# metal_mill_wiring.net
KiCad netlist of a schematic drawn in EAGLE
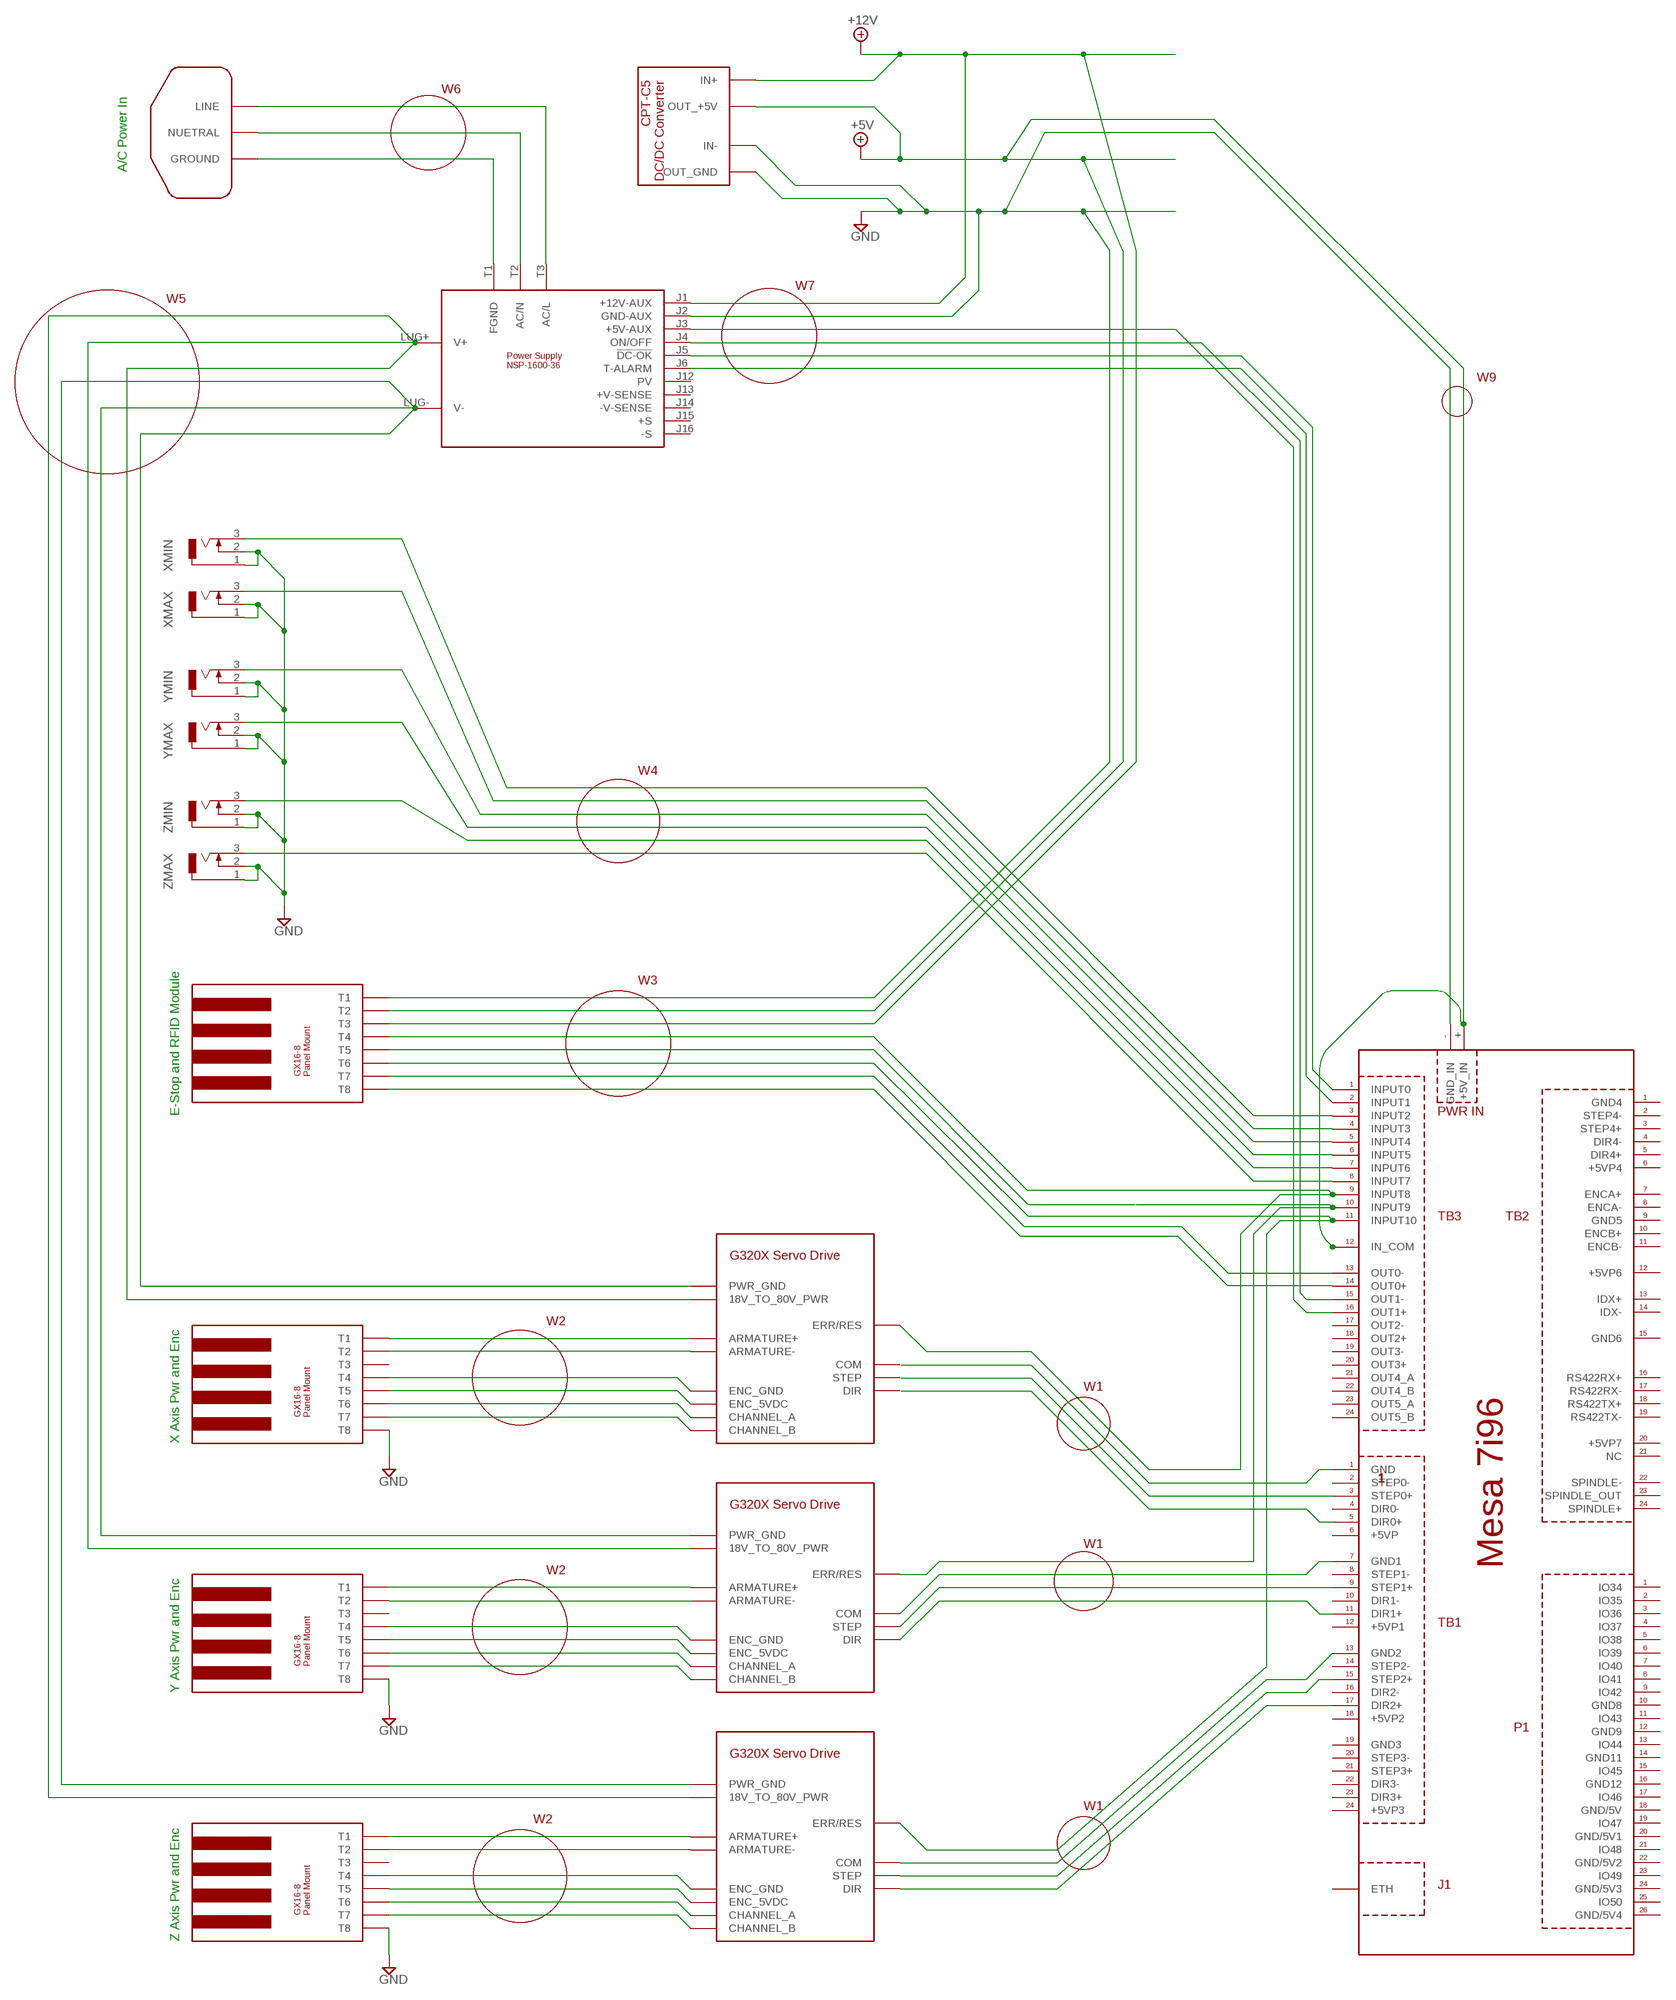
[diagram p0: schematic, sheet 1]

(export (version "E")
  (design (tool "Eeschema 10.0.6"))
  (components
    (comp (ref "U$1")
      (value "MESA_7I96")
      (footprint "eagle-import:7I96")
      (libsource (lib "eagle-import") (part "MESA_7I96"))
    )
    (comp (ref "U$2")
      (value "G320X")
      (footprint "eagle-import:G320X")
      (libsource (lib "eagle-import") (part "G320X"))
    )
    (comp (ref "U$3")
      (value "G320X")
      (footprint "eagle-import:G320X")
      (libsource (lib "eagle-import") (part "G320X"))
    )
    (comp (ref "U$4")
      (value "G320X")
      (footprint "eagle-import:G320X")
      (libsource (lib "eagle-import") (part "G320X"))
    )
    (comp (ref "U$5")
      (value "NSP-1600-36")
      (footprint "eagle-import:NSP-1600-36")
      (libsource (lib "eagle-import") (part "NSP-1600-36"))
    )
    (comp (ref "U$6")
      (value "CPT-C5")
      (footprint "eagle-import:CPT-C5")
      (libsource (lib "eagle-import") (part "CPT-C5"))
    )
    (comp (ref "U$7")
      (value "GX16-8")
      (footprint "eagle-import:GX16-8")
      (libsource (lib "eagle-import") (part "GX16-8"))
    )
    (comp (ref "U$8")
      (value "GX16-8")
      (footprint "eagle-import:GX16-8")
      (libsource (lib "eagle-import") (part "GX16-8"))
    )
    (comp (ref "U$9")
      (value "AC_JACK")
      (footprint "eagle-import:AC_JACK")
      (libsource (lib "eagle-import") (part "AC_JACK"))
    )
    (comp (ref "XMAX")
      (value "DCJ0202")
      (footprint "eagle-import:DCJ0202")
      (libsource (lib "eagle-import") (part "DCJ0202"))
    )
    (comp (ref "XMIN")
      (value "DCJ0202")
      (footprint "eagle-import:DCJ0202")
      (libsource (lib "eagle-import") (part "DCJ0202"))
    )
    (comp (ref "X_AXIS")
      (value "GX16-8")
      (footprint "eagle-import:GX16-8")
      (libsource (lib "eagle-import") (part "GX16-8"))
    )
    (comp (ref "X_AXIS1")
      (value "GX16-8")
      (footprint "eagle-import:GX16-8")
      (libsource (lib "eagle-import") (part "GX16-8"))
    )
    (comp (ref "YMAX")
      (value "DCJ0202")
      (footprint "eagle-import:DCJ0202")
      (libsource (lib "eagle-import") (part "DCJ0202"))
    )
    (comp (ref "YMIN")
      (value "DCJ0202")
      (footprint "eagle-import:DCJ0202")
      (libsource (lib "eagle-import") (part "DCJ0202"))
    )
    (comp (ref "ZMAX")
      (value "DCJ0202")
      (footprint "eagle-import:DCJ0202")
      (libsource (lib "eagle-import") (part "DCJ0202"))
    )
    (comp (ref "ZMIN")
      (value "DCJ0202")
      (footprint "eagle-import:DCJ0202")
      (libsource (lib "eagle-import") (part "DCJ0202"))
    )
  )
  (nets
    (net (code "1") (name "+5V") (class "Default")
      (node (ref "U$1") (pin "+") (pinfunction "+5V_IN_+") (pintype "bidirectional"))
      (node (ref "U$6") (pin "OUT+") (pinfunction "OUT_+5V_OUT+") (pintype "bidirectional"))
      (node (ref "X_AXIS1") (pin "P$2") (pinfunction "T2_P$2") (pintype "bidirectional"))
    )
    (net (code "2") (name "+12V") (class "Default")
      (node (ref "U$5") (pin "J1") (pinfunction "+12V-AUX_J1") (pintype "bidirectional"))
      (node (ref "U$6") (pin "IN+") (pinfunction "IN+_IN+") (pintype "bidirectional"))
      (node (ref "X_AXIS1") (pin "P$3") (pinfunction "T3_P$3") (pintype "bidirectional"))
    )
    (net (code "3") (name "/+5VP") (class "Default")
      (node (ref "U$1") (pin "TB1_6") (pinfunction "+5VP_TB1_6") (pintype "power_in"))
    )
    (net (code "4") (name "/+5VP1") (class "Default")
      (node (ref "U$1") (pin "TB1_12") (pinfunction "+5VP1_TB1_12") (pintype "power_in"))
    )
    (net (code "5") (name "/+5VP4") (class "Default")
      (node (ref "U$1") (pin "TB2_6") (pinfunction "+5VP4_TB2_6") (pintype "power_in"))
    )
    (net (code "6") (name "GND") (class "Default")
      (node (ref "U$1") (pin "-") (pinfunction "GND_IN_-") (pintype "bidirectional"))
      (node (ref "U$5") (pin "J2") (pinfunction "GND-AUX_J2") (pintype "bidirectional"))
      (node (ref "U$6") (pin "IN-") (pinfunction "IN-_IN-") (pintype "bidirectional"))
      (node (ref "U$6") (pin "OUT-") (pinfunction "OUT_GND_OUT-") (pintype "bidirectional"))
      (node (ref "U$7") (pin "P$8") (pinfunction "T8_P$8") (pintype "bidirectional"))
      (node (ref "U$8") (pin "P$8") (pinfunction "T8_P$8") (pintype "bidirectional"))
      (node (ref "XMAX") (pin "1") (pinfunction "1_1") (pintype "passive"))
      (node (ref "XMAX") (pin "2") (pinfunction "2_2") (pintype "passive"))
      (node (ref "XMIN") (pin "1") (pinfunction "1_1") (pintype "passive"))
      (node (ref "XMIN") (pin "2") (pinfunction "2_2") (pintype "passive"))
      (node (ref "X_AXIS") (pin "P$8") (pinfunction "T8_P$8") (pintype "bidirectional"))
      (node (ref "X_AXIS1") (pin "P$1") (pinfunction "T1_P$1") (pintype "bidirectional"))
      (node (ref "YMAX") (pin "1") (pinfunction "1_1") (pintype "passive"))
      (node (ref "YMAX") (pin "2") (pinfunction "2_2") (pintype "passive"))
      (node (ref "YMIN") (pin "1") (pinfunction "1_1") (pintype "passive"))
      (node (ref "YMIN") (pin "2") (pinfunction "2_2") (pintype "passive"))
      (node (ref "ZMAX") (pin "1") (pinfunction "1_1") (pintype "passive"))
      (node (ref "ZMAX") (pin "2") (pinfunction "2_2") (pintype "passive"))
      (node (ref "ZMIN") (pin "1") (pinfunction "1_1") (pintype "passive"))
      (node (ref "ZMIN") (pin "2") (pinfunction "2_2") (pintype "passive"))
    )
    (net (code "7") (name "Net-(U$1-DIR1+)") (class "Default")
      (node (ref "U$1") (pin "TB1_11") (pinfunction "DIR1+_TB1_11") (pintype "bidirectional"))
      (node (ref "U$3") (pin "P$10") (pinfunction "DIR_P$10") (pintype "bidirectional"))
    )
    (net (code "8") (name "Net-(U$1-DIR2+)") (class "Default")
      (node (ref "U$1") (pin "TB1_17") (pinfunction "DIR2+_TB1_17") (pintype "bidirectional"))
      (node (ref "U$2") (pin "P$10") (pinfunction "DIR_P$10") (pintype "bidirectional"))
    )
    (net (code "9") (name "Net-(U$1-GND1)") (class "Default")
      (node (ref "U$1") (pin "TB1_7") (pinfunction "GND1_TB1_7") (pintype "bidirectional"))
      (node (ref "U$3") (pin "P$12") (pinfunction "COM_P$12") (pintype "bidirectional"))
    )
    (net (code "10") (name "Net-(U$1-GND2)") (class "Default")
      (node (ref "U$1") (pin "TB1_13") (pinfunction "GND2_TB1_13") (pintype "bidirectional"))
      (node (ref "U$2") (pin "P$12") (pinfunction "COM_P$12") (pintype "bidirectional"))
    )
    (net (code "11") (name "Net-(U$1-INPUT0)") (class "Default")
      (node (ref "U$1") (pin "TB3_1") (pinfunction "INPUT0_TB3_1") (pintype "input"))
      (node (ref "U$5") (pin "J5") (pinfunction "~{DC-OK}_J5") (pintype "bidirectional"))
    )
    (net (code "12") (name "Net-(U$1-INPUT1)") (class "Default")
      (node (ref "U$1") (pin "TB3_2") (pinfunction "INPUT1_TB3_2") (pintype "input"))
      (node (ref "U$5") (pin "J6") (pinfunction "T-ALARM_J6") (pintype "bidirectional"))
    )
    (net (code "13") (name "Net-(U$1-INPUT2)") (class "Default")
      (node (ref "U$1") (pin "TB3_3") (pinfunction "INPUT2_TB3_3") (pintype "input"))
      (node (ref "XMIN") (pin "3") (pinfunction "3_3") (pintype "passive"))
    )
    (net (code "14") (name "Net-(U$1-INPUT3)") (class "Default")
      (node (ref "U$1") (pin "TB3_4") (pinfunction "INPUT3_TB3_4") (pintype "input"))
      (node (ref "XMAX") (pin "3") (pinfunction "3_3") (pintype "passive"))
    )
    (net (code "15") (name "Net-(U$1-INPUT4)") (class "Default")
      (node (ref "U$1") (pin "TB3_5") (pinfunction "INPUT4_TB3_5") (pintype "input"))
      (node (ref "YMIN") (pin "3") (pinfunction "3_3") (pintype "passive"))
    )
    (net (code "16") (name "Net-(U$1-INPUT5)") (class "Default")
      (node (ref "U$1") (pin "TB3_6") (pinfunction "INPUT5_TB3_6") (pintype "input"))
      (node (ref "YMAX") (pin "3") (pinfunction "3_3") (pintype "passive"))
    )
    (net (code "17") (name "Net-(U$1-INPUT6)") (class "Default")
      (node (ref "U$1") (pin "TB3_7") (pinfunction "INPUT6_TB3_7") (pintype "input"))
      (node (ref "ZMIN") (pin "3") (pinfunction "3_3") (pintype "passive"))
    )
    (net (code "18") (name "Net-(U$1-INPUT7)") (class "Default")
      (node (ref "U$1") (pin "TB3_8") (pinfunction "INPUT7_TB3_8") (pintype "input"))
      (node (ref "ZMAX") (pin "3") (pinfunction "3_3") (pintype "passive"))
    )
    (net (code "19") (name "Net-(U$1-INPUT8)") (class "Default")
      (node (ref "U$1") (pin "TB3_9") (pinfunction "INPUT8_TB3_9") (pintype "input"))
      (node (ref "U$4") (pin "P$5") (pinfunction "ERR/RES_P$5") (pintype "bidirectional"))
      (node (ref "X_AXIS1") (pin "P$4") (pinfunction "T4_P$4") (pintype "bidirectional"))
    )
    (net (code "20") (name "Net-(U$1-INPUT9)") (class "Default")
      (node (ref "U$1") (pin "TB3_10") (pinfunction "INPUT9_TB3_10") (pintype "input"))
      (node (ref "U$3") (pin "P$5") (pinfunction "ERR/RES_P$5") (pintype "bidirectional"))
    )
    (net (code "21") (name "Net-(U$1-INPUT10)") (class "Default")
      (node (ref "U$1") (pin "TB3_11") (pinfunction "INPUT10_TB3_11") (pintype "input"))
      (node (ref "U$2") (pin "P$5") (pinfunction "ERR/RES_P$5") (pintype "bidirectional"))
      (node (ref "X_AXIS1") (pin "P$6") (pinfunction "T6_P$6") (pintype "bidirectional"))
    )
    (net (code "22") (name "Net-(U$1-OUT0+)") (class "Default")
      (node (ref "U$1") (pin "TB3_14") (pinfunction "OUT0+_TB3_14") (pintype "bidirectional"))
      (node (ref "X_AXIS1") (pin "P$8") (pinfunction "T8_P$8") (pintype "bidirectional"))
    )
    (net (code "23") (name "Net-(U$1-OUT0-)") (class "Default")
      (node (ref "U$1") (pin "TB3_13") (pinfunction "OUT0-_TB3_13") (pintype "bidirectional"))
      (node (ref "X_AXIS1") (pin "P$7") (pinfunction "T7_P$7") (pintype "bidirectional"))
    )
    (net (code "24") (name "Net-(U$1-OUT1+)") (class "Default")
      (node (ref "U$1") (pin "TB3_16") (pinfunction "OUT1+_TB3_16") (pintype "bidirectional"))
      (node (ref "U$5") (pin "J3") (pinfunction "+5V-AUX_J3") (pintype "bidirectional"))
    )
    (net (code "25") (name "Net-(U$1-OUT1-)") (class "Default")
      (node (ref "U$1") (pin "TB3_15") (pinfunction "OUT1-_TB3_15") (pintype "bidirectional"))
      (node (ref "U$5") (pin "J4") (pinfunction "ON/OFF_J4") (pintype "bidirectional"))
    )
    (net (code "26") (name "Net-(U$1-STEP1+)") (class "Default")
      (node (ref "U$1") (pin "TB1_9") (pinfunction "STEP1+_TB1_9") (pintype "bidirectional"))
      (node (ref "U$3") (pin "P$11") (pinfunction "STEP_P$11") (pintype "bidirectional"))
    )
    (net (code "27") (name "Net-(U$1-STEP2+)") (class "Default")
      (node (ref "U$1") (pin "TB1_15") (pinfunction "STEP2+_TB1_15") (pintype "bidirectional"))
      (node (ref "U$2") (pin "P$11") (pinfunction "STEP_P$11") (pintype "bidirectional"))
    )
    (net (code "28") (name "Net-(U$2-18V_TO_80V_PWR)") (class "Default")
      (node (ref "U$2") (pin "P$2") (pinfunction "18V_TO_80V_PWR_P$2") (pintype "bidirectional"))
      (node (ref "U$3") (pin "P$2") (pinfunction "18V_TO_80V_PWR_P$2") (pintype "bidirectional"))
      (node (ref "U$4") (pin "P$2") (pinfunction "18V_TO_80V_PWR_P$2") (pintype "bidirectional"))
      (node (ref "U$5") (pin "LUG+") (pinfunction "V+_LUG+") (pintype "bidirectional"))
    )
    (net (code "29") (name "Net-(U$2-ARMATURE+)") (class "Default")
      (node (ref "U$2") (pin "P$4") (pinfunction "ARMATURE+_P$4") (pintype "bidirectional"))
      (node (ref "U$7") (pin "P$1") (pinfunction "T1_P$1") (pintype "bidirectional"))
    )
    (net (code "30") (name "Net-(U$2-ARMATURE-)") (class "Default")
      (node (ref "U$2") (pin "P$3") (pinfunction "ARMATURE-_P$3") (pintype "bidirectional"))
      (node (ref "U$7") (pin "P$2") (pinfunction "T2_P$2") (pintype "bidirectional"))
    )
    (net (code "31") (name "Net-(U$2-CHANNEL_A)") (class "Default")
      (node (ref "U$2") (pin "P$8") (pinfunction "CHANNEL_A_P$8") (pintype "bidirectional"))
      (node (ref "U$7") (pin "P$6") (pinfunction "T6_P$6") (pintype "bidirectional"))
    )
    (net (code "32") (name "Net-(U$2-CHANNEL_B)") (class "Default")
      (node (ref "U$2") (pin "P$9") (pinfunction "CHANNEL_B_P$9") (pintype "bidirectional"))
      (node (ref "U$7") (pin "P$7") (pinfunction "T7_P$7") (pintype "bidirectional"))
    )
    (net (code "33") (name "Net-(U$2-ENC_5VDC)") (class "Default")
      (node (ref "U$2") (pin "P$7") (pinfunction "ENC_5VDC_P$7") (pintype "bidirectional"))
      (node (ref "U$7") (pin "P$5") (pinfunction "T5_P$5") (pintype "bidirectional"))
    )
    (net (code "34") (name "Net-(U$2-ENC_GND)") (class "Default")
      (node (ref "U$2") (pin "P$6") (pinfunction "ENC_GND_P$6") (pintype "bidirectional"))
      (node (ref "U$7") (pin "P$4") (pinfunction "T4_P$4") (pintype "bidirectional"))
    )
    (net (code "35") (name "Net-(U$2-PWR_GND)") (class "Default")
      (node (ref "U$2") (pin "P$1") (pinfunction "PWR_GND_P$1") (pintype "bidirectional"))
      (node (ref "U$3") (pin "P$1") (pinfunction "PWR_GND_P$1") (pintype "bidirectional"))
      (node (ref "U$4") (pin "P$1") (pinfunction "PWR_GND_P$1") (pintype "bidirectional"))
      (node (ref "U$5") (pin "LUG-") (pinfunction "V-_LUG-") (pintype "bidirectional"))
    )
    (net (code "36") (name "Net-(U$3-ARMATURE+)") (class "Default")
      (node (ref "U$3") (pin "P$4") (pinfunction "ARMATURE+_P$4") (pintype "bidirectional"))
      (node (ref "U$8") (pin "P$1") (pinfunction "T1_P$1") (pintype "bidirectional"))
    )
    (net (code "37") (name "Net-(U$3-ARMATURE-)") (class "Default")
      (node (ref "U$3") (pin "P$3") (pinfunction "ARMATURE-_P$3") (pintype "bidirectional"))
      (node (ref "U$8") (pin "P$2") (pinfunction "T2_P$2") (pintype "bidirectional"))
    )
    (net (code "38") (name "Net-(U$3-CHANNEL_A)") (class "Default")
      (node (ref "U$3") (pin "P$8") (pinfunction "CHANNEL_A_P$8") (pintype "bidirectional"))
      (node (ref "U$8") (pin "P$6") (pinfunction "T6_P$6") (pintype "bidirectional"))
    )
    (net (code "39") (name "Net-(U$3-CHANNEL_B)") (class "Default")
      (node (ref "U$3") (pin "P$9") (pinfunction "CHANNEL_B_P$9") (pintype "bidirectional"))
      (node (ref "U$8") (pin "P$7") (pinfunction "T7_P$7") (pintype "bidirectional"))
    )
    (net (code "40") (name "Net-(U$3-ENC_5VDC)") (class "Default")
      (node (ref "U$3") (pin "P$7") (pinfunction "ENC_5VDC_P$7") (pintype "bidirectional"))
      (node (ref "U$8") (pin "P$5") (pinfunction "T5_P$5") (pintype "bidirectional"))
    )
    (net (code "41") (name "Net-(U$3-ENC_GND)") (class "Default")
      (node (ref "U$3") (pin "P$6") (pinfunction "ENC_GND_P$6") (pintype "bidirectional"))
      (node (ref "U$8") (pin "P$4") (pinfunction "T4_P$4") (pintype "bidirectional"))
    )
    (net (code "42") (name "Net-(U$4-ARMATURE+)") (class "Default")
      (node (ref "U$4") (pin "P$4") (pinfunction "ARMATURE+_P$4") (pintype "bidirectional"))
      (node (ref "X_AXIS") (pin "P$1") (pinfunction "T1_P$1") (pintype "bidirectional"))
    )
    (net (code "43") (name "Net-(U$4-ARMATURE-)") (class "Default")
      (node (ref "U$4") (pin "P$3") (pinfunction "ARMATURE-_P$3") (pintype "bidirectional"))
      (node (ref "X_AXIS") (pin "P$2") (pinfunction "T2_P$2") (pintype "bidirectional"))
    )
    (net (code "44") (name "Net-(U$4-CHANNEL_A)") (class "Default")
      (node (ref "U$4") (pin "P$8") (pinfunction "CHANNEL_A_P$8") (pintype "bidirectional"))
      (node (ref "X_AXIS") (pin "P$6") (pinfunction "T6_P$6") (pintype "bidirectional"))
    )
    (net (code "45") (name "Net-(U$4-CHANNEL_B)") (class "Default")
      (node (ref "U$4") (pin "P$9") (pinfunction "CHANNEL_B_P$9") (pintype "bidirectional"))
      (node (ref "X_AXIS") (pin "P$7") (pinfunction "T7_P$7") (pintype "bidirectional"))
    )
    (net (code "46") (name "Net-(U$4-ENC_5VDC)") (class "Default")
      (node (ref "U$4") (pin "P$7") (pinfunction "ENC_5VDC_P$7") (pintype "bidirectional"))
      (node (ref "X_AXIS") (pin "P$5") (pinfunction "T5_P$5") (pintype "bidirectional"))
    )
    (net (code "47") (name "Net-(U$4-ENC_GND)") (class "Default")
      (node (ref "U$4") (pin "P$6") (pinfunction "ENC_GND_P$6") (pintype "bidirectional"))
      (node (ref "X_AXIS") (pin "P$4") (pinfunction "T4_P$4") (pintype "bidirectional"))
    )
    (net (code "48") (name "Net-(U$5-AC{slash}L)") (class "Default")
      (node (ref "U$5") (pin "T3") (pinfunction "AC/L_T3") (pintype "bidirectional"))
      (node (ref "U$9") (pin "LINE") (pinfunction "LINE_LINE") (pintype "bidirectional"))
    )
    (net (code "49") (name "Net-(U$5-AC{slash}N)") (class "Default")
      (node (ref "U$5") (pin "T2") (pinfunction "AC/N_T2") (pintype "bidirectional"))
      (node (ref "U$9") (pin "NUETRAL") (pinfunction "NUETRAL_NUETRAL") (pintype "bidirectional"))
    )
    (net (code "50") (name "Net-(U$5-FGND)") (class "Default")
      (node (ref "U$5") (pin "T1") (pinfunction "FGND_T1") (pintype "bidirectional"))
      (node (ref "U$9") (pin "GROUND") (pinfunction "GROUND_GROUND") (pintype "bidirectional"))
    )
    (net (code "51") (name "unconnected-(U$1-+5VP2-PadTB1_18)") (class "Default")
      (node (ref "U$1") (pin "TB1_18") (pinfunction "+5VP2_TB1_18") (pintype "bidirectional"))
    )
    (net (code "52") (name "unconnected-(U$1-+5VP3-PadTB1_24)") (class "Default")
      (node (ref "U$1") (pin "TB1_24") (pinfunction "+5VP3_TB1_24") (pintype "bidirectional"))
    )
    (net (code "53") (name "unconnected-(U$1-+5VP6-PadTB2_12)") (class "Default")
      (node (ref "U$1") (pin "TB2_12") (pinfunction "+5VP6_TB2_12") (pintype "bidirectional"))
    )
    (net (code "54") (name "unconnected-(U$1-+5VP7-PadTB2_20)") (class "Default")
      (node (ref "U$1") (pin "TB2_20") (pinfunction "+5VP7_TB2_20") (pintype "bidirectional"))
    )
    (net (code "55") (name "unconnected-(U$1-DIR0+-PadTB1_5)") (class "Default")
      (node (ref "U$1") (pin "TB1_5") (pinfunction "DIR0+_TB1_5") (pintype "bidirectional"))
    )
    (net (code "56") (name "unconnected-(U$1-DIR0--PadTB1_4)") (class "Default")
      (node (ref "U$1") (pin "TB1_4") (pinfunction "DIR0-_TB1_4") (pintype "bidirectional"))
    )
    (net (code "57") (name "unconnected-(U$1-DIR1--PadTB1_10)") (class "Default")
      (node (ref "U$1") (pin "TB1_10") (pinfunction "DIR1-_TB1_10") (pintype "bidirectional"))
    )
    (net (code "58") (name "unconnected-(U$1-DIR2--PadTB1_16)") (class "Default")
      (node (ref "U$1") (pin "TB1_16") (pinfunction "DIR2-_TB1_16") (pintype "bidirectional"))
    )
    (net (code "59") (name "unconnected-(U$1-DIR3+-PadTB1_23)") (class "Default")
      (node (ref "U$1") (pin "TB1_23") (pinfunction "DIR3+_TB1_23") (pintype "bidirectional"))
    )
    (net (code "60") (name "unconnected-(U$1-DIR3--PadTB1_22)") (class "Default")
      (node (ref "U$1") (pin "TB1_22") (pinfunction "DIR3-_TB1_22") (pintype "bidirectional"))
    )
    (net (code "61") (name "unconnected-(U$1-DIR4+-PadTB2_5)") (class "Default")
      (node (ref "U$1") (pin "TB2_5") (pinfunction "DIR4+_TB2_5") (pintype "bidirectional"))
    )
    (net (code "62") (name "unconnected-(U$1-DIR4--PadTB2_4)") (class "Default")
      (node (ref "U$1") (pin "TB2_4") (pinfunction "DIR4-_TB2_4") (pintype "bidirectional"))
    )
    (net (code "63") (name "unconnected-(U$1-ENCA+-PadTB2_7)") (class "Default")
      (node (ref "U$1") (pin "TB2_7") (pinfunction "ENCA+_TB2_7") (pintype "bidirectional"))
    )
    (net (code "64") (name "unconnected-(U$1-ENCA--PadTB2_8)") (class "Default")
      (node (ref "U$1") (pin "TB2_8") (pinfunction "ENCA-_TB2_8") (pintype "bidirectional"))
    )
    (net (code "65") (name "unconnected-(U$1-ENCB+-PadTB2_10)") (class "Default")
      (node (ref "U$1") (pin "TB2_10") (pinfunction "ENCB+_TB2_10") (pintype "bidirectional"))
    )
    (net (code "66") (name "unconnected-(U$1-ENCB--PadTB2_11)") (class "Default")
      (node (ref "U$1") (pin "TB2_11") (pinfunction "ENCB-_TB2_11") (pintype "bidirectional"))
    )
    (net (code "67") (name "unconnected-(U$1-ETH-PadJ1)") (class "Default")
      (node (ref "U$1") (pin "J1") (pinfunction "ETH_J1") (pintype "bidirectional"))
    )
    (net (code "68") (name "unconnected-(U$1-GND-PadTB1_1)") (class "Default")
      (node (ref "U$1") (pin "TB1_1") (pinfunction "GND_TB1_1") (pintype "bidirectional"))
    )
    (net (code "69") (name "unconnected-(U$1-GND3-PadTB1_19)") (class "Default")
      (node (ref "U$1") (pin "TB1_19") (pinfunction "GND3_TB1_19") (pintype "bidirectional"))
    )
    (net (code "70") (name "unconnected-(U$1-GND4-PadTB2_1)") (class "Default")
      (node (ref "U$1") (pin "TB2_1") (pinfunction "GND4_TB2_1") (pintype "bidirectional"))
    )
    (net (code "71") (name "unconnected-(U$1-GND5-PadTB2_9)") (class "Default")
      (node (ref "U$1") (pin "TB2_9") (pinfunction "GND5_TB2_9") (pintype "bidirectional"))
    )
    (net (code "72") (name "unconnected-(U$1-GND6-PadTB2_15)") (class "Default")
      (node (ref "U$1") (pin "TB2_15") (pinfunction "GND6_TB2_15") (pintype "bidirectional"))
    )
    (net (code "73") (name "unconnected-(U$1-GND8-PadP1_10)") (class "Default")
      (node (ref "U$1") (pin "P1_10") (pinfunction "GND8_P1_10") (pintype "bidirectional"))
    )
    (net (code "74") (name "unconnected-(U$1-GND9-PadP1_12)") (class "Default")
      (node (ref "U$1") (pin "P1_12") (pinfunction "GND9_P1_12") (pintype "bidirectional"))
    )
    (net (code "75") (name "unconnected-(U$1-GND11-PadP1_16)") (class "Default")
      (node (ref "U$1") (pin "P1_16") (pinfunction "GND11_P1_16") (pintype "bidirectional"))
    )
    (net (code "76") (name "unconnected-(U$1-GND12-PadP1_14)") (class "Default")
      (node (ref "U$1") (pin "P1_14") (pinfunction "GND12_P1_14") (pintype "bidirectional"))
    )
    (net (code "77") (name "unconnected-(U$1-GND{slash}5V-PadP1_22)") (class "Default")
      (node (ref "U$1") (pin "P1_22") (pinfunction "GND/5V_P1_22") (pintype "bidirectional"))
    )
    (net (code "78") (name "unconnected-(U$1-GND{slash}5V1-PadP1_18)") (class "Default")
      (node (ref "U$1") (pin "P1_18") (pinfunction "GND/5V1_P1_18") (pintype "bidirectional"))
    )
    (net (code "79") (name "unconnected-(U$1-GND{slash}5V2-PadP1_20)") (class "Default")
      (node (ref "U$1") (pin "P1_20") (pinfunction "GND/5V2_P1_20") (pintype "bidirectional"))
    )
    (net (code "80") (name "unconnected-(U$1-GND{slash}5V3-PadP1_24)") (class "Default")
      (node (ref "U$1") (pin "P1_24") (pinfunction "GND/5V3_P1_24") (pintype "bidirectional"))
    )
    (net (code "81") (name "unconnected-(U$1-GND{slash}5V4-PadP1_26)") (class "Default")
      (node (ref "U$1") (pin "P1_26") (pinfunction "GND/5V4_P1_26") (pintype "bidirectional"))
    )
    (net (code "82") (name "unconnected-(U$1-IDX+-PadTB2_13)") (class "Default")
      (node (ref "U$1") (pin "TB2_13") (pinfunction "IDX+_TB2_13") (pintype "bidirectional"))
    )
    (net (code "83") (name "unconnected-(U$1-IDX--PadTB2_14)") (class "Default")
      (node (ref "U$1") (pin "TB2_14") (pinfunction "IDX-_TB2_14") (pintype "bidirectional"))
    )
    (net (code "84") (name "unconnected-(U$1-IN_COM-PadTB3_12)") (class "Default")
      (node (ref "U$1") (pin "TB3_12") (pinfunction "IN_COM_TB3_12") (pintype "input"))
    )
    (net (code "85") (name "unconnected-(U$1-IO34-PadP1_1)") (class "Default")
      (node (ref "U$1") (pin "P1_1") (pinfunction "IO34_P1_1") (pintype "bidirectional"))
    )
    (net (code "86") (name "unconnected-(U$1-IO35-PadP1_2)") (class "Default")
      (node (ref "U$1") (pin "P1_2") (pinfunction "IO35_P1_2") (pintype "bidirectional"))
    )
    (net (code "87") (name "unconnected-(U$1-IO36-PadP1_3)") (class "Default")
      (node (ref "U$1") (pin "P1_3") (pinfunction "IO36_P1_3") (pintype "bidirectional"))
    )
    (net (code "88") (name "unconnected-(U$1-IO37-PadP1_4)") (class "Default")
      (node (ref "U$1") (pin "P1_4") (pinfunction "IO37_P1_4") (pintype "bidirectional"))
    )
    (net (code "89") (name "unconnected-(U$1-IO38-PadP1_5)") (class "Default")
      (node (ref "U$1") (pin "P1_5") (pinfunction "IO38_P1_5") (pintype "bidirectional"))
    )
    (net (code "90") (name "unconnected-(U$1-IO39-PadP1_6)") (class "Default")
      (node (ref "U$1") (pin "P1_6") (pinfunction "IO39_P1_6") (pintype "bidirectional"))
    )
    (net (code "91") (name "unconnected-(U$1-IO40-PadP1_7)") (class "Default")
      (node (ref "U$1") (pin "P1_7") (pinfunction "IO40_P1_7") (pintype "bidirectional"))
    )
    (net (code "92") (name "unconnected-(U$1-IO41-PadP1_8)") (class "Default")
      (node (ref "U$1") (pin "P1_8") (pinfunction "IO41_P1_8") (pintype "bidirectional"))
    )
    (net (code "93") (name "unconnected-(U$1-IO42-PadP1_9)") (class "Default")
      (node (ref "U$1") (pin "P1_9") (pinfunction "IO42_P1_9") (pintype "bidirectional"))
    )
    (net (code "94") (name "unconnected-(U$1-IO43-PadP1_11)") (class "Default")
      (node (ref "U$1") (pin "P1_11") (pinfunction "IO43_P1_11") (pintype "bidirectional"))
    )
    (net (code "95") (name "unconnected-(U$1-IO44-PadP1_13)") (class "Default")
      (node (ref "U$1") (pin "P1_13") (pinfunction "IO44_P1_13") (pintype "bidirectional"))
    )
    (net (code "96") (name "unconnected-(U$1-IO45-PadP1_15)") (class "Default")
      (node (ref "U$1") (pin "P1_15") (pinfunction "IO45_P1_15") (pintype "bidirectional"))
    )
    (net (code "97") (name "unconnected-(U$1-IO46-PadP1_17)") (class "Default")
      (node (ref "U$1") (pin "P1_17") (pinfunction "IO46_P1_17") (pintype "bidirectional"))
    )
    (net (code "98") (name "unconnected-(U$1-IO47-PadP1_19)") (class "Default")
      (node (ref "U$1") (pin "P1_19") (pinfunction "IO47_P1_19") (pintype "bidirectional"))
    )
    (net (code "99") (name "unconnected-(U$1-IO48-PadP1_21)") (class "Default")
      (node (ref "U$1") (pin "P1_21") (pinfunction "IO48_P1_21") (pintype "bidirectional"))
    )
    (net (code "100") (name "unconnected-(U$1-IO49-PadP1_23)") (class "Default")
      (node (ref "U$1") (pin "P1_23") (pinfunction "IO49_P1_23") (pintype "bidirectional"))
    )
    (net (code "101") (name "unconnected-(U$1-IO50-PadP1_25)") (class "Default")
      (node (ref "U$1") (pin "P1_25") (pinfunction "IO50_P1_25") (pintype "bidirectional"))
    )
    (net (code "102") (name "unconnected-(U$1-NC-PadTB2_21)") (class "Default")
      (node (ref "U$1") (pin "TB2_21") (pinfunction "NC_TB2_21") (pintype "bidirectional"))
    )
    (net (code "103") (name "unconnected-(U$1-OUT2+-PadTB3_18)") (class "Default")
      (node (ref "U$1") (pin "TB3_18") (pinfunction "OUT2+_TB3_18") (pintype "bidirectional"))
    )
    (net (code "104") (name "unconnected-(U$1-OUT2--PadTB3_17)") (class "Default")
      (node (ref "U$1") (pin "TB3_17") (pinfunction "OUT2-_TB3_17") (pintype "bidirectional"))
    )
    (net (code "105") (name "unconnected-(U$1-OUT3+-PadTB3_20)") (class "Default")
      (node (ref "U$1") (pin "TB3_20") (pinfunction "OUT3+_TB3_20") (pintype "bidirectional"))
    )
    (net (code "106") (name "unconnected-(U$1-OUT3--PadTB3_19)") (class "Default")
      (node (ref "U$1") (pin "TB3_19") (pinfunction "OUT3-_TB3_19") (pintype "bidirectional"))
    )
    (net (code "107") (name "unconnected-(U$1-OUT4_A-PadTB3_21)") (class "Default")
      (node (ref "U$1") (pin "TB3_21") (pinfunction "OUT4_A_TB3_21") (pintype "bidirectional"))
    )
    (net (code "108") (name "unconnected-(U$1-OUT4_B-PadTB3_22)") (class "Default")
      (node (ref "U$1") (pin "TB3_22") (pinfunction "OUT4_B_TB3_22") (pintype "bidirectional"))
    )
    (net (code "109") (name "unconnected-(U$1-OUT5_A-PadTB3_23)") (class "Default")
      (node (ref "U$1") (pin "TB3_23") (pinfunction "OUT5_A_TB3_23") (pintype "bidirectional"))
    )
    (net (code "110") (name "unconnected-(U$1-OUT5_B-PadTB3_24)") (class "Default")
      (node (ref "U$1") (pin "TB3_24") (pinfunction "OUT5_B_TB3_24") (pintype "bidirectional"))
    )
    (net (code "111") (name "unconnected-(U$1-RS422RX+-PadTB2_16)") (class "Default")
      (node (ref "U$1") (pin "TB2_16") (pinfunction "RS422RX+_TB2_16") (pintype "bidirectional"))
    )
    (net (code "112") (name "unconnected-(U$1-RS422RX--PadTB2_17)") (class "Default")
      (node (ref "U$1") (pin "TB2_17") (pinfunction "RS422RX-_TB2_17") (pintype "bidirectional"))
    )
    (net (code "113") (name "unconnected-(U$1-RS422TX+-PadTB2_18)") (class "Default")
      (node (ref "U$1") (pin "TB2_18") (pinfunction "RS422TX+_TB2_18") (pintype "bidirectional"))
    )
    (net (code "114") (name "unconnected-(U$1-RS422TX--PadTB2_19)") (class "Default")
      (node (ref "U$1") (pin "TB2_19") (pinfunction "RS422TX-_TB2_19") (pintype "bidirectional"))
    )
    (net (code "115") (name "unconnected-(U$1-SPINDLE+-PadTB2_24)") (class "Default")
      (node (ref "U$1") (pin "TB2_24") (pinfunction "SPINDLE+_TB2_24") (pintype "bidirectional"))
    )
    (net (code "116") (name "unconnected-(U$1-SPINDLE--PadTB2_22)") (class "Default")
      (node (ref "U$1") (pin "TB2_22") (pinfunction "SPINDLE-_TB2_22") (pintype "bidirectional"))
    )
    (net (code "117") (name "unconnected-(U$1-SPINDLE_OUT-PadTB2_23)") (class "Default")
      (node (ref "U$1") (pin "TB2_23") (pinfunction "SPINDLE_OUT_TB2_23") (pintype "bidirectional"))
    )
    (net (code "118") (name "unconnected-(U$1-STEP0+-PadTB1_3)") (class "Default")
      (node (ref "U$1") (pin "TB1_3") (pinfunction "STEP0+_TB1_3") (pintype "bidirectional"))
    )
    (net (code "119") (name "unconnected-(U$1-STEP0--PadTB1_2)") (class "Default")
      (node (ref "U$1") (pin "TB1_2") (pinfunction "STEP0-_TB1_2") (pintype "bidirectional"))
    )
    (net (code "120") (name "unconnected-(U$1-STEP1--PadTB1_8)") (class "Default")
      (node (ref "U$1") (pin "TB1_8") (pinfunction "STEP1-_TB1_8") (pintype "bidirectional"))
    )
    (net (code "121") (name "unconnected-(U$1-STEP2--PadTB1_14)") (class "Default")
      (node (ref "U$1") (pin "TB1_14") (pinfunction "STEP2-_TB1_14") (pintype "bidirectional"))
    )
    (net (code "122") (name "unconnected-(U$1-STEP3+-PadTB1_21)") (class "Default")
      (node (ref "U$1") (pin "TB1_21") (pinfunction "STEP3+_TB1_21") (pintype "bidirectional"))
    )
    (net (code "123") (name "unconnected-(U$1-STEP3--PadTB1_20)") (class "Default")
      (node (ref "U$1") (pin "TB1_20") (pinfunction "STEP3-_TB1_20") (pintype "bidirectional"))
    )
    (net (code "124") (name "unconnected-(U$1-STEP4+-PadTB2_3)") (class "Default")
      (node (ref "U$1") (pin "TB2_3") (pinfunction "STEP4+_TB2_3") (pintype "bidirectional"))
    )
    (net (code "125") (name "unconnected-(U$1-STEP4--PadTB2_2)") (class "Default")
      (node (ref "U$1") (pin "TB2_2") (pinfunction "STEP4-_TB2_2") (pintype "bidirectional"))
    )
    (net (code "126") (name "unconnected-(U$4-COM-PadP$12)") (class "Default")
      (node (ref "U$4") (pin "P$12") (pinfunction "COM_P$12") (pintype "bidirectional"))
    )
    (net (code "127") (name "unconnected-(U$4-DIR-PadP$10)") (class "Default")
      (node (ref "U$4") (pin "P$10") (pinfunction "DIR_P$10") (pintype "bidirectional"))
    )
    (net (code "128") (name "unconnected-(U$4-STEP-PadP$11)") (class "Default")
      (node (ref "U$4") (pin "P$11") (pinfunction "STEP_P$11") (pintype "bidirectional"))
    )
    (net (code "129") (name "unconnected-(U$5-+S-PadJ15)") (class "Default")
      (node (ref "U$5") (pin "J15") (pinfunction "+S_J15") (pintype "bidirectional"))
    )
    (net (code "130") (name "unconnected-(U$5-+V-SENSE-PadJ13)") (class "Default")
      (node (ref "U$5") (pin "J13") (pinfunction "+V-SENSE_J13") (pintype "bidirectional"))
    )
    (net (code "131") (name "unconnected-(U$5--S-PadJ16)") (class "Default")
      (node (ref "U$5") (pin "J16") (pinfunction "-S_J16") (pintype "bidirectional"))
    )
    (net (code "132") (name "unconnected-(U$5--V-SENSE-PadJ14)") (class "Default")
      (node (ref "U$5") (pin "J14") (pinfunction "-V-SENSE_J14") (pintype "bidirectional"))
    )
    (net (code "133") (name "unconnected-(U$5-PV-PadJ12)") (class "Default")
      (node (ref "U$5") (pin "J12") (pinfunction "PV_J12") (pintype "bidirectional"))
    )
    (net (code "134") (name "unconnected-(U$7-T3-PadP$3)") (class "Default")
      (node (ref "U$7") (pin "P$3") (pinfunction "T3_P$3") (pintype "bidirectional"))
    )
    (net (code "135") (name "unconnected-(U$8-T3-PadP$3)") (class "Default")
      (node (ref "U$8") (pin "P$3") (pinfunction "T3_P$3") (pintype "bidirectional"))
    )
    (net (code "136") (name "unconnected-(X_AXIS-T3-PadP$3)") (class "Default")
      (node (ref "X_AXIS") (pin "P$3") (pinfunction "T3_P$3") (pintype "bidirectional"))
    )
    (net (code "137") (name "unconnected-(X_AXIS1-T5-PadP$5)") (class "Default")
      (node (ref "X_AXIS1") (pin "P$5") (pinfunction "T5_P$5") (pintype "bidirectional"))
    )
  )
)
